# TXS0102YZPR.net
KiCad netlist of a schematic drawn in Altium Designer
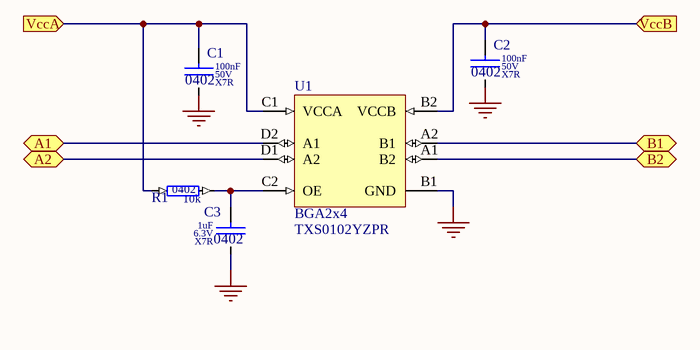
[diagram p0: TXS0102YZPR.SchDoc]

(export (version "E")
  (design (tool "Eeschema 10.0.6"))
  (components
    (comp (ref "C1")
      (value "100nF")
      (footprint "C_0402_1005")
      (description "Capacitor")
      (fields
        (field (name "DIELECTRIC") "X7R")
        (field (name "VOLTAGE") "50V")
        (field (name "SCH_FOOTPRINT") "0402")
        (field (name "PART NUMBER") "C_100nF_50V_X7R_0402_10")
        (field (name "MANUFACTURER") "Murata")
      )
      (libsource (lib "Library") (part "C"))
    )
    (comp (ref "C2")
      (value "100nF")
      (footprint "C_0402_1005")
      (description "Capacitor")
      (fields
        (field (name "DIELECTRIC") "X7R")
        (field (name "VOLTAGE") "50V")
        (field (name "SCH_FOOTPRINT") "0402")
        (field (name "PART NUMBER") "C_100nF_50V_X7R_0402_10")
        (field (name "MANUFACTURER") "Murata")
      )
      (libsource (lib "Library") (part "C"))
    )
    (comp (ref "C3")
      (value "1uF")
      (footprint "C_0402_1005")
      (description "Capacitor")
      (fields
        (field (name "DIELECTRIC") "X7R")
        (field (name "VOLTAGE") "6.3V")
        (field (name "SCH_FOOTPRINT") "0402")
        (field (name "PART NUMBER") "C_1uF_6.3V_X7R_0402_10")
        (field (name "MANUFACTURER") "Murata")
      )
      (libsource (lib "Library") (part "C"))
    )
    (comp (ref "R1")
      (value "10k")
      (footprint "R_0402_1005")
      (fields
        (field (name "SCH_FOOTPRINT") "0402")
        (field (name "PART NUMBER") "R_10k_0402_1")
        (field (name "VOLTAGE") "50V")
        (field (name "POWER") "63mW")
      )
      (libsource (lib "Library") (part "R"))
    )
    (comp (ref "U1")
      (value "TXS0102YZPR")
      (footprint "BGA_2x4x0.5mm")
      (fields
        (field (name "SCH_FOOTPRINT") "BGA2x4")
        (field (name "PART NUMBER") "U_TXS0102YZPR")
        (field (name "MANUFACTURER") "Texas Instruments")
        (field (name "Comment") "Level shifter")
      )
      (libsource (lib "Library") (part "U_TXS0102YZPR"))
    )
  )
  (nets
    (net (code "1") (name "/A1") (class "Default")
      (node (ref "U1") (pin "D2") (pinfunction "A1_D2") (pintype "bidirectional"))
    )
    (net (code "2") (name "/A2") (class "Default")
      (node (ref "U1") (pin "D1") (pinfunction "A2_D1") (pintype "bidirectional"))
    )
    (net (code "3") (name "/B1") (class "Default")
      (node (ref "U1") (pin "A2") (pinfunction "B1_A2") (pintype "bidirectional"))
    )
    (net (code "4") (name "/B2") (class "Default")
      (node (ref "U1") (pin "A1") (pinfunction "B2_A1") (pintype "bidirectional"))
    )
    (net (code "5") (name "/VccA") (class "Default")
      (node (ref "C1") (pin "1") (pinfunction "1_1") (pintype "passive"))
      (node (ref "R1") (pin "1") (pinfunction "1_1") (pintype "input"))
      (node (ref "U1") (pin "C1") (pinfunction "VCCA_C1") (pintype "input"))
    )
    (net (code "6") (name "/VccB") (class "Default")
      (node (ref "C2") (pin "1") (pinfunction "1_1") (pintype "passive"))
      (node (ref "U1") (pin "B2") (pinfunction "VCCB_B2") (pintype "input"))
    )
    (net (code "7") (name "GND") (class "Default")
      (node (ref "C1") (pin "2") (pinfunction "2_2") (pintype "passive"))
      (node (ref "C2") (pin "2") (pinfunction "2_2") (pintype "passive"))
      (node (ref "C3") (pin "2") (pinfunction "2_2") (pintype "passive"))
      (node (ref "U1") (pin "B1") (pinfunction "GND_B1") (pintype "power_in"))
    )
    (net (code "8") (name "Net-(U1-OE)") (class "Default")
      (node (ref "C3") (pin "1") (pinfunction "1_1") (pintype "passive"))
      (node (ref "R1") (pin "2") (pinfunction "2_2") (pintype "output"))
      (node (ref "U1") (pin "C2") (pinfunction "OE_C2") (pintype "input"))
    )
  )
)
